# EXTERNAL_VOLTAGE_DETECTOR.net
KiCad netlist of a schematic drawn in Altium Designer
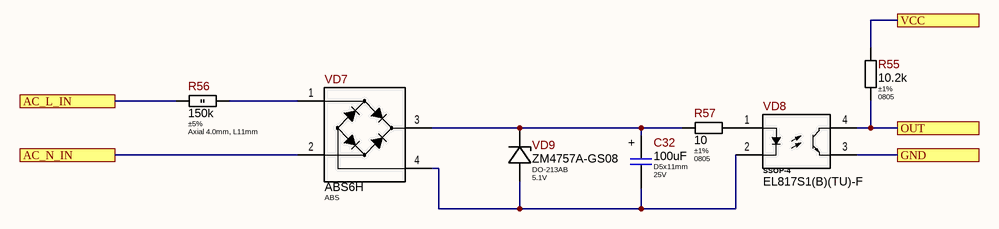
[diagram p0: EXTERNAL_VOLTAGE_DETECTOR.SchDoc]

(export (version "E")
  (design (tool "Eeschema 10.0.6"))
  (components
    (comp (ref "C32")
      (value "100uF")
      (footprint "CAP-AE-PTH-50D05x110H15")
      (description "100uF 25V ±20% D5x11mm 105℃ Aluminum Electrolytic Capacitor")
      (fields
        (field (name "PACKAGE") "D5x11mm")
        (field (name "VOLTAGE") "25V")
        (field (name "PART NUMBER") "KRM-025V101MC110-T/A2")
        (field (name "MANUFACTURER") "Koshin")
      )
      (libsource (lib "capacitors") (part "KRM-025V101MC110-T/A2"))
    )
    (comp (ref "R55")
      (value "10.2k")
      (footprint "R_ANY_CHIP_0805_MED")
      (description "10.2 kOhms ±1%, 1/8W 0805 Thick Film Resistor")
      (fields
        (field (name "TOLERANCE") "±1%")
        (field (name "PACKAGE") "0805")
        (field (name "PART NUMBER") "RC0805FR-0710K2L")
        (field (name "MANUFACTURER") "Yageo")
      )
      (libsource (lib "resistors") (part "RC0805FR-0710K2L"))
    )
    (comp (ref "R56")
      (value "150k")
      (footprint "MOR200S-Series")
      (description "150k Ohm ±5%, 2W d4.0mm L11mm Axial Through Hole, Metal Oxide Resistor, Al2O3")
      (fields
        (field (name "TOLERANCE") "±5%")
        (field (name "PACKAGE") "Axial 4.0mm, L11mm")
        (field (name "PART NUMBER") "MOR200SJTB-10R")
        (field (name "MANUFACTURER") "Hitano")
      )
      (libsource (lib "resistors") (part "MOR200SJTB-10R"))
    )
    (comp (ref "R57")
      (value "10")
      (footprint "R_ANY_CHIP_0805_MED")
      (description "10 Ohms ±1%, 1/8W 0805 Thick Film Resistor")
      (fields
        (field (name "TOLERANCE") "±1%")
        (field (name "PACKAGE") "0805")
        (field (name "PART NUMBER") "RC0805FR-0710RL")
        (field (name "MANUFACTURER") "Yageo")
      )
      (libsource (lib "resistors") (part "RC0805FR-0710RL"))
    )
    (comp (ref "VD7")
      (value "ABS6H")
      (footprint "ABSxx-Series")
      (description "1A, 600V Standard Bridge Rectifier, ABS Package")
      (fields
        (field (name "PART NUMBER") "ABS6H")
        (field (name "PACKAGE") "ABS")
        (field (name "MANUFACTURER") "Taiwan Semiconductor")
        (field (name "VOLTAGE") "600V")
      )
      (libsource (lib "diodes") (part "ABS6H"))
    )
    (comp (ref "VD8")
      (value "EL817S1(B)(TU)-F")
      (footprint "EL-817S1-(x)(xx)")
      (description "1-Channel Photocoupler, 5kV, 130-260% CTR, SSOP-4")
      (fields
        (field (name "PACKAGE") "SSOP-4")
        (field (name "PART NUMBER") "EL817S1(B)(TU)-F")
        (field (name "MANUFACTURER") "Everlight Electronics")
      )
      (libsource (lib "opto") (part "EL817S1(B)(TU)-F"))
    )
    (comp (ref "VD9")
      (value "ZM4757A-GS08")
      (footprint "DO-213AB")
      (description "Zener Diode 5.1V, 1W, ±5%, 5uA Reverse Current, DO-213AB")
      (fields
        (field (name "PART NUMBER") "ZM4757A-GS08")
        (field (name "PACKAGE") "DO-213AB")
        (field (name "VOLTAGE") "5.1V")
        (field (name "MANUFACTURER") "Vishay Semiconductor")
      )
      (libsource (lib "diodes") (part "ZM4757A-GS08"))
    )
  )
  (nets
    (net (code "1") (name "/AC_L_IN") (class "Default") (node (ref "R56") (pin "1") (pintype "passive")))
    (net (code "2") (name "/AC_N_IN") (class "Default")
      (node (ref "VD7") (pin "2") (pinfunction "~_2") (pintype "passive"))
    )
    (net (code "3") (name "/GND") (class "Default")
      (node (ref "VD8") (pin "3") (pinfunction "Emitter_3") (pintype "passive"))
    )
    (net (code "4") (name "/OUT") (class "Default")
      (node (ref "R55") (pin "2") (pintype "passive"))
      (node (ref "VD8") (pin "4") (pinfunction "Collector_4") (pintype "passive"))
    )
    (net (code "5") (name "/VCC") (class "Default") (node (ref "R55") (pin "1") (pintype "passive")))
    (net (code "6") (name "Net-(R56-Pad2)") (class "Default")
      (node (ref "R56") (pin "2") (pintype "passive"))
      (node (ref "VD7") (pin "1") (pinfunction "~_1") (pintype "passive"))
    )
    (net (code "7") (name "Net-(VD7-+)") (class "Default")
      (node (ref "C32") (pin "1") (pinfunction "1_1") (pintype "passive"))
      (node (ref "R57") (pin "1") (pintype "passive"))
      (node (ref "VD7") (pin "3") (pinfunction "+_3") (pintype "passive"))
      (node (ref "VD9") (pin "CA") (pintype "passive"))
    )
    (net (code "8") (name "Net-(VD7--)") (class "Default")
      (node (ref "C32") (pin "2") (pinfunction "2_2") (pintype "passive"))
      (node (ref "VD7") (pin "4") (pinfunction "-_4") (pintype "passive"))
      (node (ref "VD8") (pin "2") (pinfunction "Cathode_2") (pintype "passive"))
      (node (ref "VD9") (pin "AN") (pintype "passive"))
    )
    (net (code "9") (name "Net-(VD8-Anode)") (class "Default")
      (node (ref "R57") (pin "2") (pintype "passive"))
      (node (ref "VD8") (pin "1") (pinfunction "Anode_1") (pintype "passive"))
    )
  )
)
